# gestureBoard.net
KiCad netlist of a schematic drawn in EAGLE
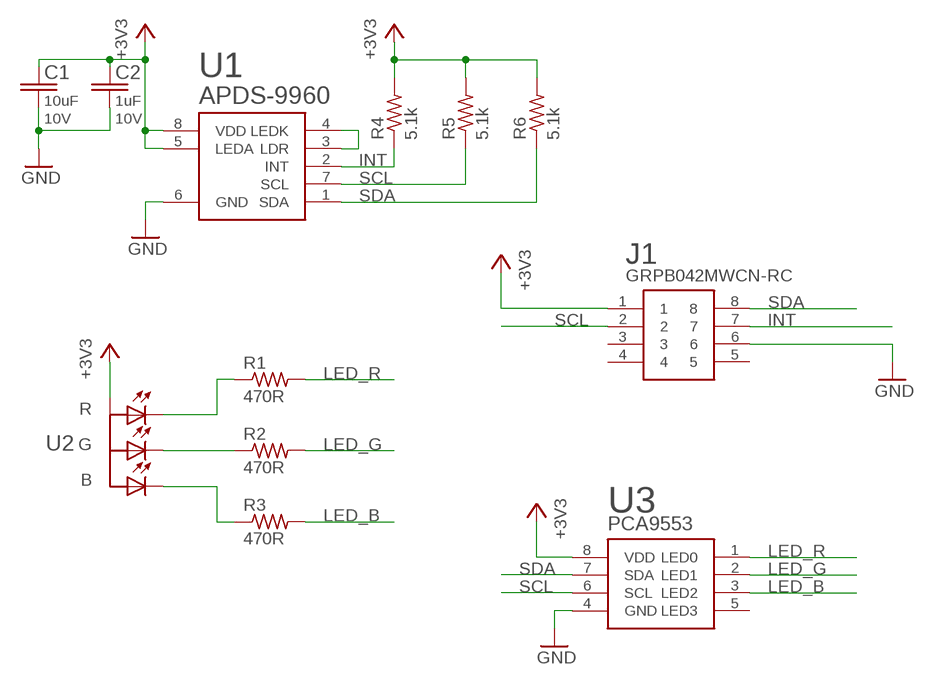
[diagram p0: schematic, sheet 1]

(export (version "E")
  (design (tool "Eeschema 10.0.6"))
  (components
    (comp (ref "C1")
      (value "10uF")
      (footprint "eagle-import:C0603")
      (fields (field (name "RATING") "10V"))
      (libsource (lib "eagle-import") (part "GRM188R61A106KE69D"))
    )
    (comp (ref "C2")
      (value "1uF")
      (footprint "eagle-import:C0402")
      (fields (field (name "RATING") "10V"))
      (libsource (lib "eagle-import") (part "CL05A105MP5NNNC"))
    )
    (comp (ref "J1")
      (value "GRPB042MWCN-RC")
      (footprint "eagle-import:GRPB042MWCN-RC")
      (libsource (lib "eagle-import") (part "GRPB042MWCN-RC"))
    )
    (comp (ref "R1")
      (value "470R")
      (footprint "eagle-import:R0402")
      (libsource (lib "eagle-import") (part "RC0402JR-07470RL"))
    )
    (comp (ref "R2")
      (value "470R")
      (footprint "eagle-import:R0402")
      (libsource (lib "eagle-import") (part "RC0402JR-07470RL"))
    )
    (comp (ref "R3")
      (value "470R")
      (footprint "eagle-import:R0402")
      (libsource (lib "eagle-import") (part "RC0402JR-07470RL"))
    )
    (comp (ref "R4")
      (value "5.1k")
      (footprint "eagle-import:R0402")
      (libsource (lib "eagle-import") (part "RC0402JR-075K1L"))
    )
    (comp (ref "R5")
      (value "5.1k")
      (footprint "eagle-import:R0402")
      (libsource (lib "eagle-import") (part "RC0402JR-075K1L"))
    )
    (comp (ref "R6")
      (value "5.1k")
      (footprint "eagle-import:R0402")
      (libsource (lib "eagle-import") (part "RC0402JR-075K1L"))
    )
    (comp (ref "U1")
      (value "APDS-9960")
      (footprint "eagle-import:APDS-9960")
      (libsource (lib "eagle-import") (part "APDS-9960"))
    )
    (comp (ref "U2")
      (value "ASMB-MTB0-0A3A2")
      (footprint "eagle-import:ASMB-MTB0_LED")
      (libsource (lib "eagle-import") (part "ASMB-MTB0-0A3A2"))
    )
    (comp (ref "U3")
      (value "PCA9553TSSOP8")
      (footprint "eagle-import:SOP65P490X110-8")
      (libsource (lib "eagle-import") (part "PCA9553TSSOP8"))
    )
  )
  (nets
    (net (code "1") (name "+3V3") (class "Default")
      (node (ref "C1") (pin "1") (pinfunction "1_1") (pintype "bidirectional"))
      (node (ref "C2") (pin "1") (pinfunction "1_1") (pintype "bidirectional"))
      (node (ref "J1") (pin "1") (pinfunction "1_1") (pintype "bidirectional"))
      (node (ref "R4") (pin "2") (pinfunction "2_2") (pintype "passive"))
      (node (ref "R5") (pin "2") (pinfunction "2_2") (pintype "passive"))
      (node (ref "R6") (pin "2") (pinfunction "2_2") (pintype "passive"))
      (node (ref "U1") (pin "5") (pinfunction "LEDA_5") (pintype "bidirectional"))
      (node (ref "U1") (pin "8") (pinfunction "VDD_8") (pintype "bidirectional"))
      (node (ref "U2") (pin "1") (pinfunction "A_1") (pintype "passive"))
      (node (ref "U3") (pin "8") (pinfunction "VDD_8") (pintype "bidirectional"))
    )
    (net (code "2") (name "/INT") (class "Default")
      (node (ref "J1") (pin "7") (pinfunction "7_7") (pintype "bidirectional"))
      (node (ref "R4") (pin "1") (pinfunction "1_1") (pintype "passive"))
      (node (ref "U1") (pin "2") (pinfunction "INT_2") (pintype "bidirectional"))
    )
    (net (code "3") (name "/LED_B") (class "Default")
      (node (ref "R3") (pin "2") (pinfunction "2_2") (pintype "passive"))
      (node (ref "U3") (pin "3") (pinfunction "LED2_3") (pintype "bidirectional"))
    )
    (net (code "4") (name "/LED_G") (class "Default")
      (node (ref "R2") (pin "2") (pinfunction "2_2") (pintype "passive"))
      (node (ref "U3") (pin "2") (pinfunction "LED1_2") (pintype "bidirectional"))
    )
    (net (code "5") (name "/LED_R") (class "Default")
      (node (ref "R1") (pin "2") (pinfunction "2_2") (pintype "passive"))
      (node (ref "U3") (pin "1") (pinfunction "LED0_1") (pintype "bidirectional"))
    )
    (net (code "6") (name "/SCL") (class "Default")
      (node (ref "J1") (pin "2") (pinfunction "2_2") (pintype "bidirectional"))
      (node (ref "R5") (pin "1") (pinfunction "1_1") (pintype "passive"))
      (node (ref "U1") (pin "7") (pinfunction "SCL_7") (pintype "bidirectional"))
      (node (ref "U3") (pin "6") (pinfunction "SCL_6") (pintype "bidirectional"))
    )
    (net (code "7") (name "/SDA") (class "Default")
      (node (ref "J1") (pin "8") (pinfunction "8_8") (pintype "bidirectional"))
      (node (ref "R6") (pin "1") (pinfunction "1_1") (pintype "passive"))
      (node (ref "U1") (pin "1") (pinfunction "SDA_1") (pintype "bidirectional"))
      (node (ref "U3") (pin "7") (pinfunction "SDA_7") (pintype "bidirectional"))
    )
    (net (code "8") (name "GND") (class "Default")
      (node (ref "C1") (pin "2") (pinfunction "2_2") (pintype "bidirectional"))
      (node (ref "C2") (pin "2") (pinfunction "2_2") (pintype "bidirectional"))
      (node (ref "J1") (pin "6") (pinfunction "6_6") (pintype "bidirectional"))
      (node (ref "U1") (pin "6") (pinfunction "GND_6") (pintype "bidirectional"))
      (node (ref "U3") (pin "4") (pinfunction "GND_4") (pintype "bidirectional"))
    )
    (net (code "9") (name "Net-(U1-LDR)") (class "Default")
      (node (ref "U1") (pin "3") (pinfunction "LDR_3") (pintype "bidirectional"))
      (node (ref "U1") (pin "4") (pinfunction "LEDK_4") (pintype "bidirectional"))
    )
    (net (code "10") (name "Net-(U2-B)") (class "Default")
      (node (ref "R3") (pin "1") (pinfunction "1_1") (pintype "passive"))
      (node (ref "U2") (pin "2") (pinfunction "B_2") (pintype "passive"))
    )
    (net (code "11") (name "Net-(U2-G)") (class "Default")
      (node (ref "R2") (pin "1") (pinfunction "1_1") (pintype "passive"))
      (node (ref "U2") (pin "3") (pinfunction "G_3") (pintype "passive"))
    )
    (net (code "12") (name "Net-(U2-R)") (class "Default")
      (node (ref "R1") (pin "1") (pinfunction "1_1") (pintype "passive"))
      (node (ref "U2") (pin "4") (pinfunction "R_4") (pintype "passive"))
    )
    (net (code "13") (name "unconnected-(J1-Pad3)") (class "Default")
      (node (ref "J1") (pin "3") (pinfunction "3_3") (pintype "bidirectional"))
    )
    (net (code "14") (name "unconnected-(J1-Pad4)") (class "Default")
      (node (ref "J1") (pin "4") (pinfunction "4_4") (pintype "bidirectional"))
    )
    (net (code "15") (name "unconnected-(J1-Pad5)") (class "Default")
      (node (ref "J1") (pin "5") (pinfunction "5_5") (pintype "bidirectional"))
    )
    (net (code "16") (name "unconnected-(U3-LED3-Pad5)") (class "Default")
      (node (ref "U3") (pin "5") (pinfunction "LED3_5") (pintype "bidirectional"))
    )
  )
)
